# Tractive_System_Board_Rev6.net
KiCad netlist of a schematic drawn in EAGLE
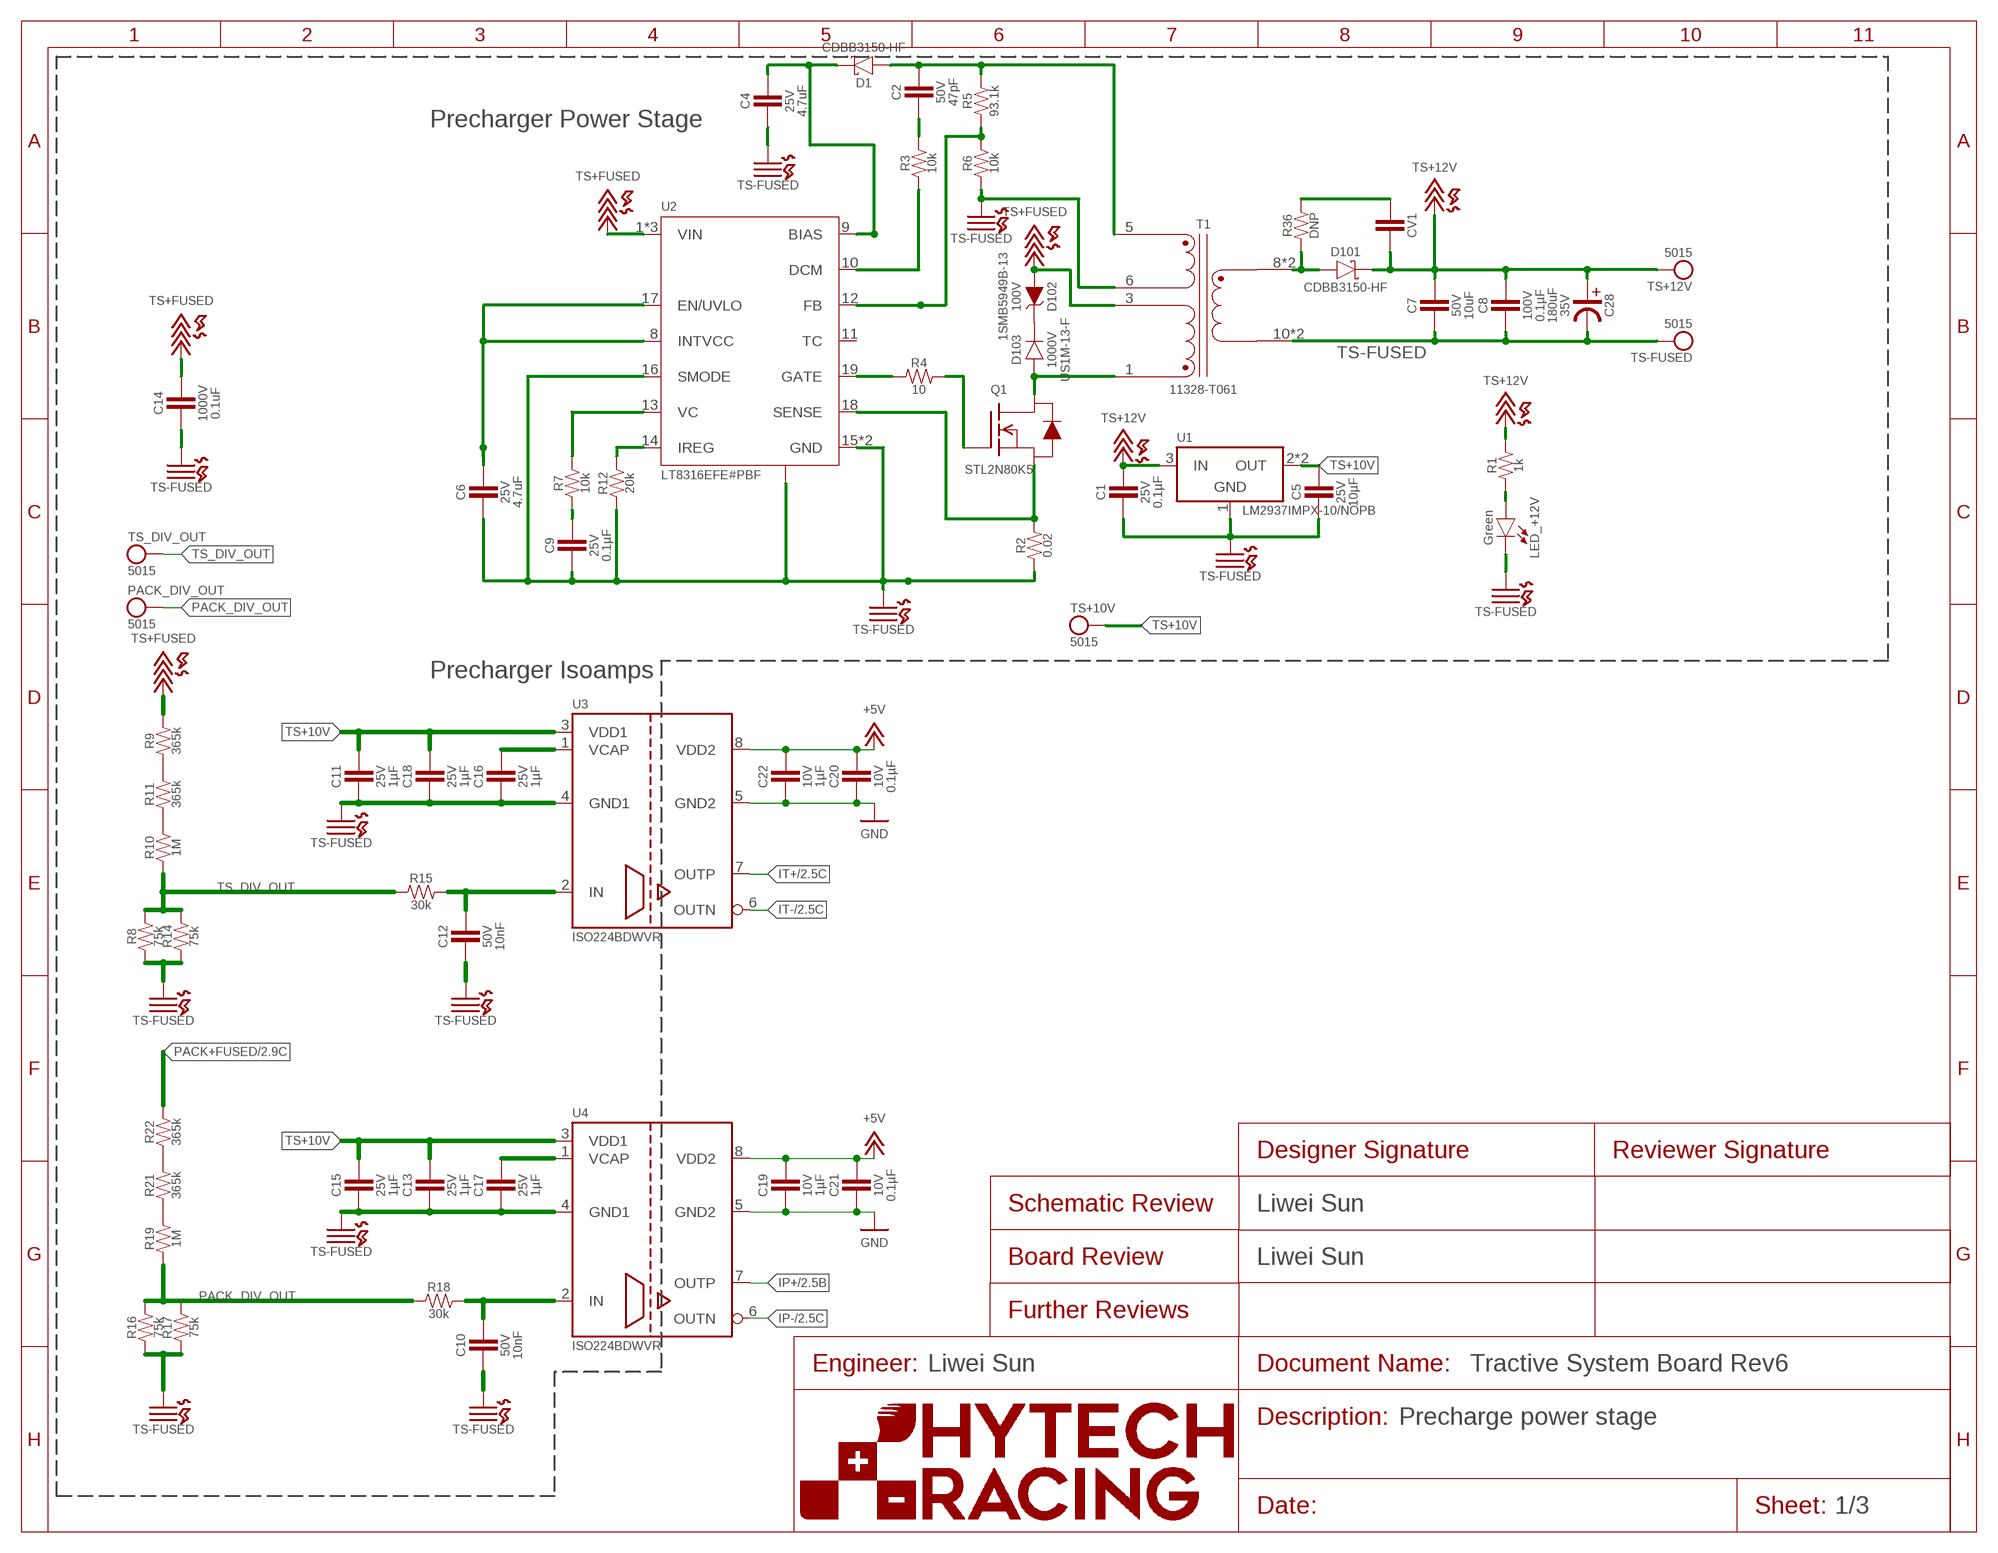
[diagram p0: schematic, sheet 1]
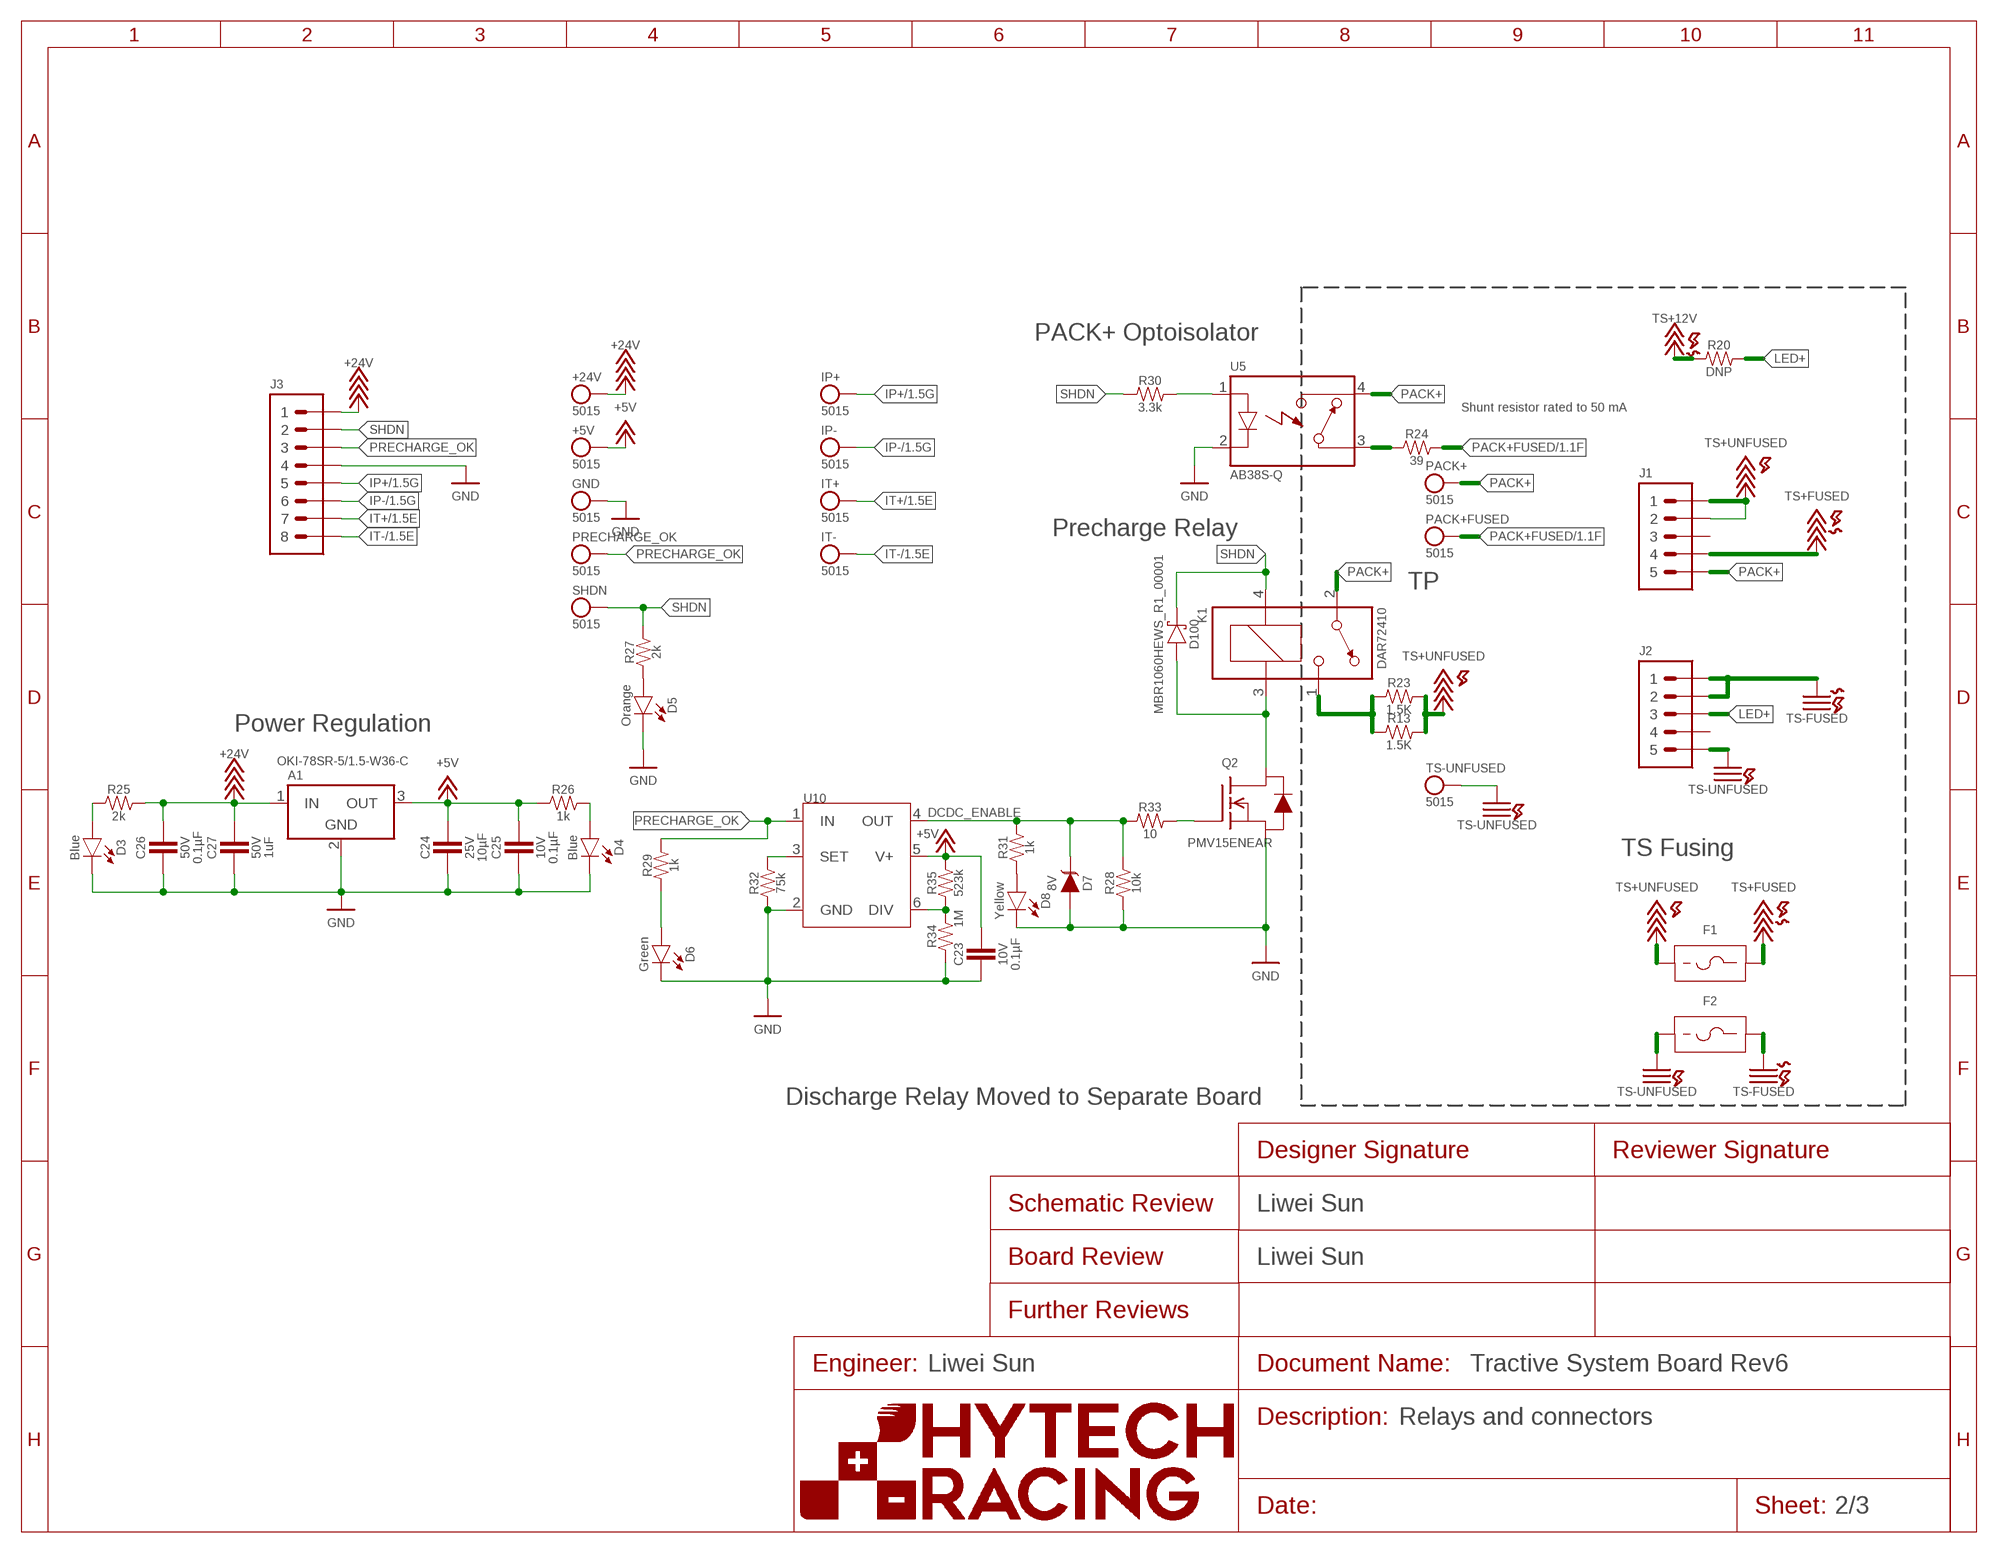
[diagram p1: schematic, sheet 2]
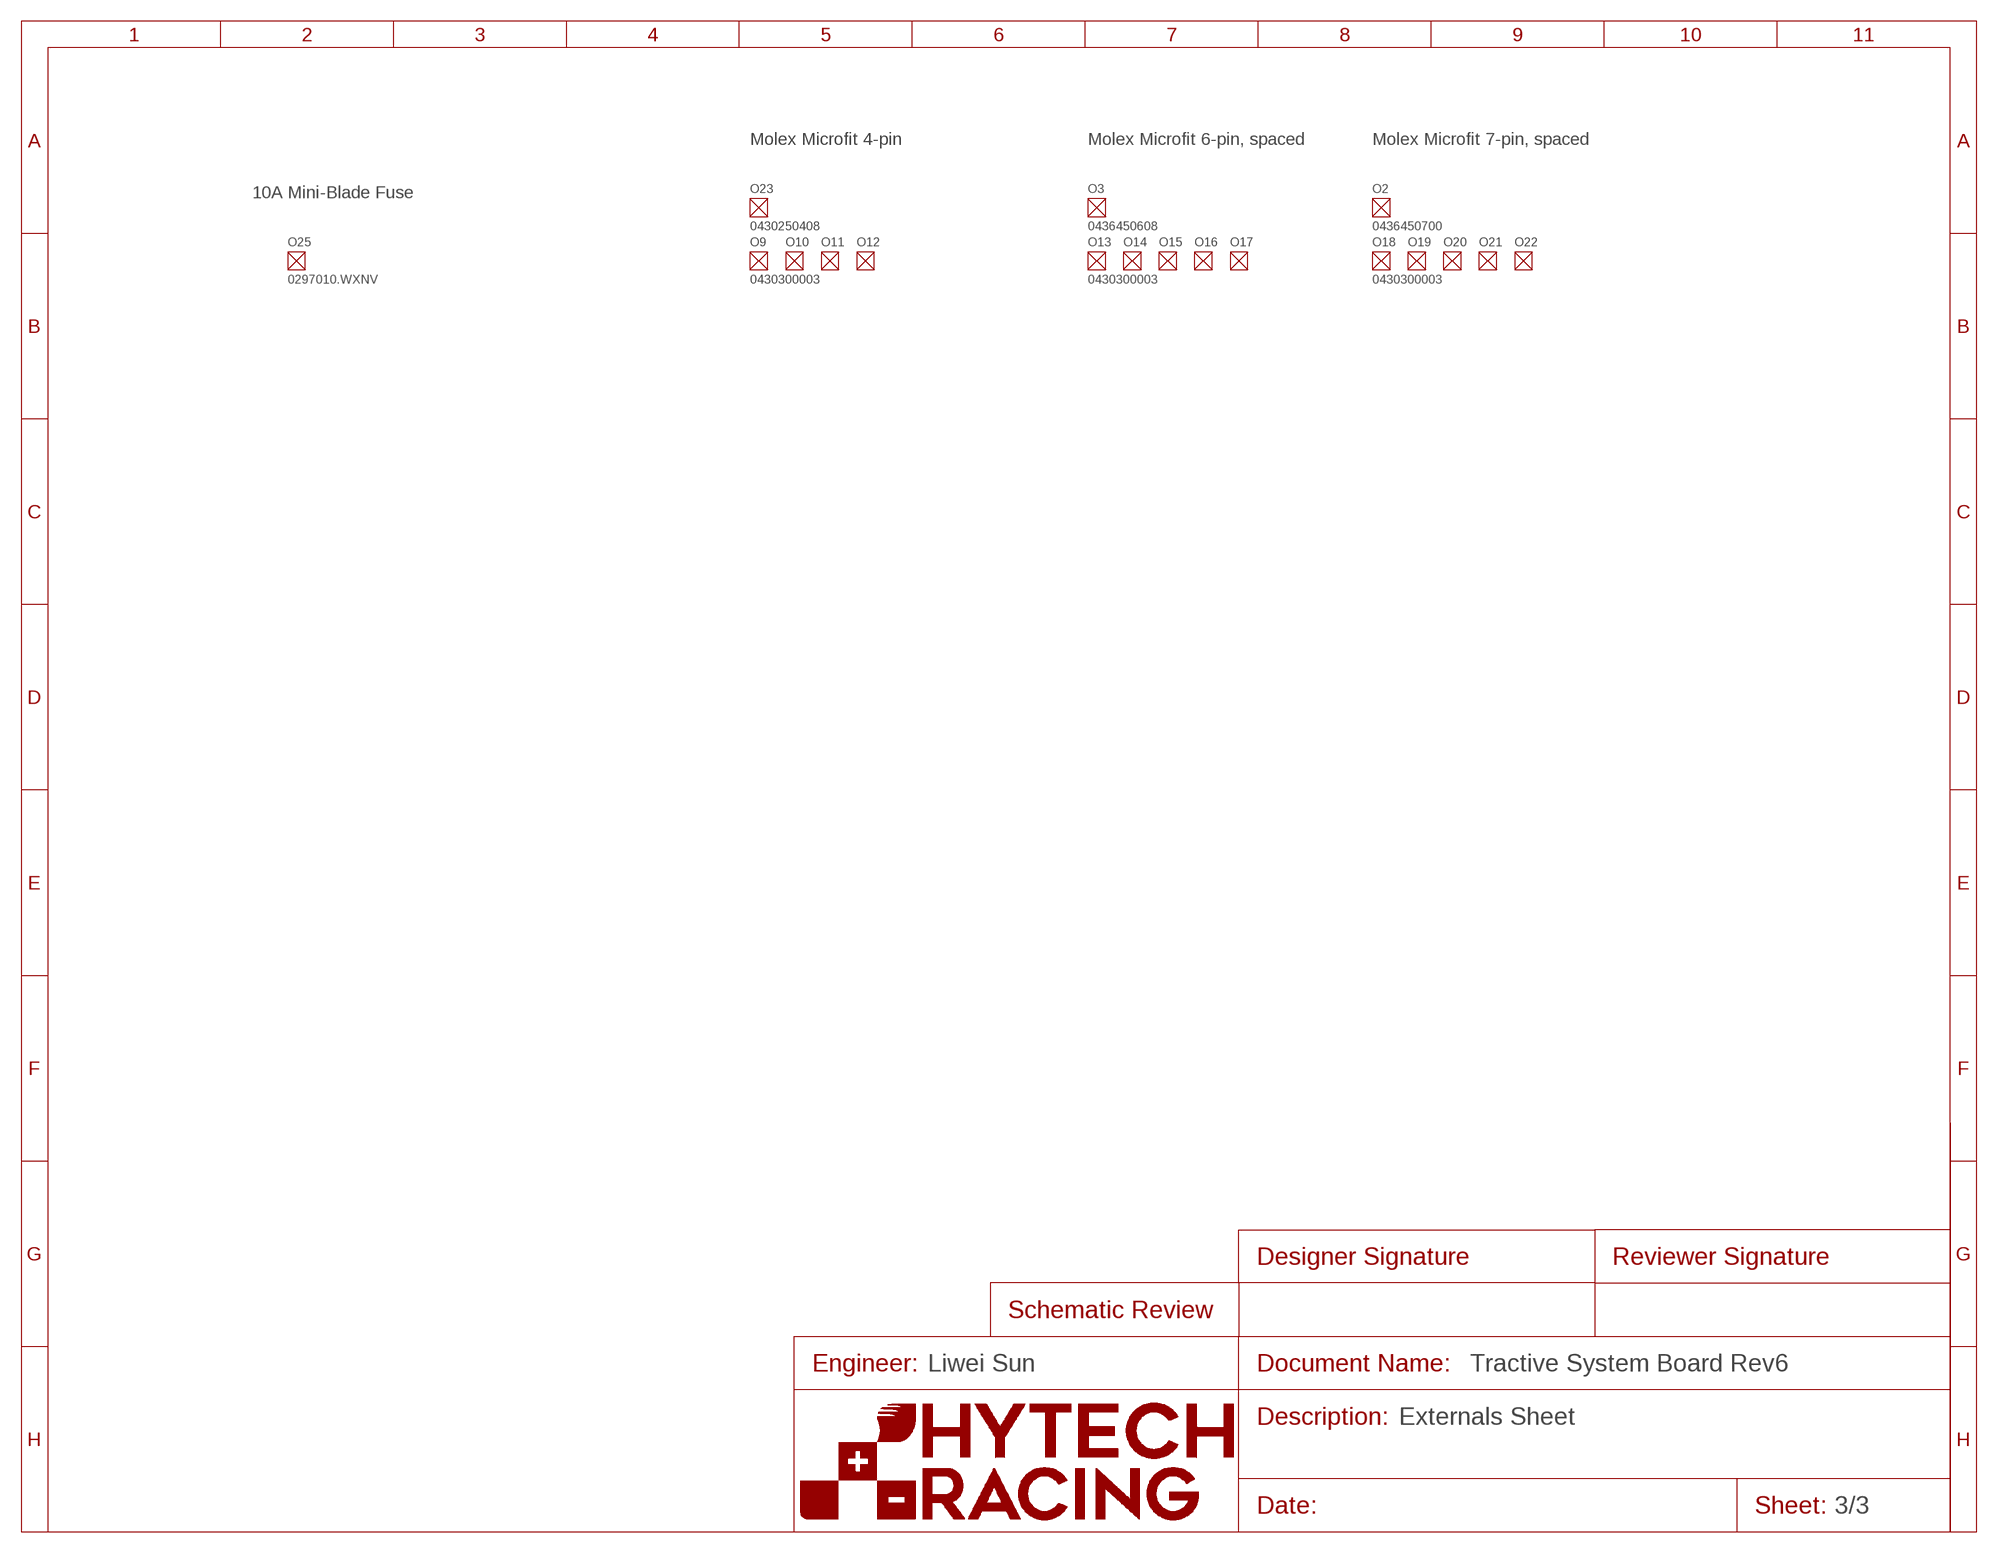
[diagram p2: schematic, sheet 3]

(export (version "E")
  (design (tool "Eeschema 10.0.6"))
  (components
    (comp (ref "+5V")
      (value "TEST_POINT")
      (footprint "eagle-import:5015")
      (fields (field (name "MPN") "5015") (field (name "MANUFACTURER") "Keystone Electronics"))
      (libsource (lib "eagle-import") (part "TEST_POINT"))
    )
    (comp (ref "+24V")
      (value "TEST_POINT")
      (footprint "eagle-import:5015")
      (fields (field (name "MPN") "5015") (field (name "MANUFACTURER") "Keystone Electronics"))
      (libsource (lib "eagle-import") (part "TEST_POINT"))
    )
    (comp (ref "A1")
      (value "VOLTAGE_REGULATOR_MODULE_OKI-78SR_5V")
      (footprint "eagle-import:OKI-78SR")
      (fields
        (field (name "MANUFACTURER") "Murata Power Solutions Inc.")
        (field (name "MPN") "OKI-78SR-5/1.5-W36-C")
      )
      (libsource (lib "eagle-import") (part "VOLTAGE_REGULATOR_MODULE_?_OKI-78SR5V"))
    )
    (comp (ref "C23")
      (value "CAPACITOR_0603_10V_0.1UF")
      (footprint "eagle-import:0603-CAP")
      (fields
        (field (name "CAPACITANCE") "0.1µF")
        (field (name "MANUFACTURER") "Vishay Vitramon")
        (field (name "MPN") "VJ0603Y104JXQPW1BC")
        (field (name "TOLERANCE") "5%")
        (field (name "VOLTAGE") "10V")
      )
      (libsource (lib "eagle-import") (part "CAPACITOR_?_060310V_0.1UF"))
    )
    (comp (ref "C24")
      (value "CAPACITOR_0603_25V_10UF")
      (footprint "eagle-import:0603-CAP")
      (fields
        (field (name "CAPACITANCE") "10µF")
        (field (name "MANUFACTURER") "Murata Electronics")
        (field (name "MPN") "GRM188R61E106MA73D")
        (field (name "TOLERANCE") "20%")
        (field (name "VOLTAGE") "25V")
      )
      (libsource (lib "eagle-import") (part "CAPACITOR_?_060325V_10UF"))
    )
    (comp (ref "C25")
      (value "CAPACITOR_0603_10V_0.1UF")
      (footprint "eagle-import:0603-CAP")
      (fields
        (field (name "CAPACITANCE") "0.1µF")
        (field (name "MANUFACTURER") "Vishay Vitramon")
        (field (name "MPN") "VJ0603Y104JXQPW1BC")
        (field (name "TOLERANCE") "5%")
        (field (name "VOLTAGE") "10V")
      )
      (libsource (lib "eagle-import") (part "CAPACITOR_?_060310V_0.1UF"))
    )
    (comp (ref "C26")
      (value "CAPACITOR_0603_50V_0.1UF")
      (footprint "eagle-import:0603-CAP")
      (fields
        (field (name "CAPACITANCE") "0.1µF")
        (field (name "MANUFACTURER") "Yageo")
        (field (name "MPN") "CC0603KRX7R9BB104")
        (field (name "TOLERANCE") "10%")
        (field (name "VOLTAGE") "50V")
      )
      (libsource (lib "eagle-import") (part "CAPACITOR_?_060350V_0.1UF"))
    )
    (comp (ref "C27")
      (value "CAPACITOR_0603_50V_1UF")
      (footprint "eagle-import:0603-CAP")
      (fields
        (field (name "CAPACITANCE") "1uF")
        (field (name "MANUFACTURER") "Taiyo Yuden")
        (field (name "MPN") "UMK107BJ105KA-T")
        (field (name "TOLERANCE") "10%")
        (field (name "VOLTAGE") "50V")
      )
      (libsource (lib "eagle-import") (part "CAPACITOR_?_060350V_1UF"))
    )
    (comp (ref "D3")
      (value "LED_0603_BLUE")
      (footprint "eagle-import:0603-LED")
      (fields
        (field (name "COLOR") "Blue")
        (field (name "MANUFACTURER") "Kingbright")
        (field (name "MPN") "APT1608VBC/D")
      )
      (libsource (lib "eagle-import") (part "LED_?_0603BLUE"))
    )
    (comp (ref "D4")
      (value "LED_0603_BLUE")
      (footprint "eagle-import:0603-LED")
      (fields
        (field (name "COLOR") "Blue")
        (field (name "MANUFACTURER") "Kingbright")
        (field (name "MPN") "APT1608VBC/D")
      )
      (libsource (lib "eagle-import") (part "LED_?_0603BLUE"))
    )
    (comp (ref "D5")
      (value "LED_0603_ORANGE")
      (footprint "eagle-import:0603-LED")
      (fields
        (field (name "COLOR") "Orange")
        (field (name "MANUFACTURER") "Kingbright")
        (field (name "MPN") "APT1608SECK")
      )
      (libsource (lib "eagle-import") (part "LED_?_0603ORANGE"))
    )
    (comp (ref "D6")
      (value "LED_0603_GREEN")
      (footprint "eagle-import:0603-LED")
      (fields
        (field (name "COLOR") "Green")
        (field (name "MANUFACTURER") "Kingbright")
        (field (name "MPN") "APT1608ZGCK")
      )
      (libsource (lib "eagle-import") (part "LED_?_0603GREEN"))
    )
    (comp (ref "D7")
      (value "TVS__8V")
      (footprint "eagle-import:SOT-23")
      (fields
        (field (name "MANUFACTURER") "Vishay General Semiconductor - Diodes Division")
        (field (name "MPN") "GSOT08-E3-08")
        (field (name "VOLTAGE") "8V")
      )
      (libsource (lib "eagle-import") (part "TVS_?_8V"))
    )
    (comp (ref "D8")
      (value "LED_0603_YELLOW")
      (footprint "eagle-import:0603-LED")
      (fields
        (field (name "COLOR") "Yellow")
        (field (name "MANUFACTURER") "Kingbright")
        (field (name "MPN") "APT1608SYCK/J3-PRV")
      )
      (libsource (lib "eagle-import") (part "LED_?_0603YELLOW"))
    )
    (comp (ref "D100")
      (value "SCHOTTKY_SOD323_60V")
      (footprint "eagle-import:SOD-323")
      (fields
        (field (name "MANUFACTURER") "Panjit International Inc.")
        (field (name "MPN") "MBR1060HEWS_R1_00001")
        (field (name "VOLTAGE") "60V")
      )
      (libsource (lib "eagle-import") (part "SCHOTTKY_?_SOD32360V"))
    )
    (comp (ref "F1")
      (value "FUSE_HOLDER_122")
      (footprint "eagle-import:122")
      (fields (field (name "MPN") "01220088Z") (field (name "MANUFACTURER") "Littelfuse"))
      (libsource (lib "eagle-import") (part "FUSE_HOLDER_122"))
    )
    (comp (ref "F2")
      (value "FUSE_HOLDER_122")
      (footprint "eagle-import:122")
      (fields (field (name "MPN") "01220088Z") (field (name "MANUFACTURER") "Littelfuse"))
      (libsource (lib "eagle-import") (part "FUSE_HOLDER_122"))
    )
    (comp (ref "GND")
      (value "TEST_POINT")
      (footprint "eagle-import:5015")
      (fields (field (name "MPN") "5015") (field (name "MANUFACTURER") "Keystone Electronics"))
      (libsource (lib "eagle-import") (part "TEST_POINT"))
    )
    (comp (ref "IP+")
      (value "TEST_POINT")
      (footprint "eagle-import:5015")
      (fields (field (name "MPN") "5015") (field (name "MANUFACTURER") "Keystone Electronics"))
      (libsource (lib "eagle-import") (part "TEST_POINT"))
    )
    (comp (ref "IP-")
      (value "TEST_POINT")
      (footprint "eagle-import:5015")
      (fields (field (name "MPN") "5015") (field (name "MANUFACTURER") "Keystone Electronics"))
      (libsource (lib "eagle-import") (part "TEST_POINT"))
    )
    (comp (ref "IT+")
      (value "TEST_POINT")
      (footprint "eagle-import:5015")
      (fields (field (name "MPN") "5015") (field (name "MANUFACTURER") "Keystone Electronics"))
      (libsource (lib "eagle-import") (part "TEST_POINT"))
    )
    (comp (ref "IT-")
      (value "TEST_POINT")
      (footprint "eagle-import:5015")
      (fields (field (name "MPN") "5015") (field (name "MANUFACTURER") "Keystone Electronics"))
      (libsource (lib "eagle-import") (part "TEST_POINT"))
    )
    (comp (ref "J1")
      (value "CONNECTOR-5_MICRO_V7S_")
      (footprint "eagle-import:MOLEX_MICROFIT_PTH_VERTICAL_07_SINGLE_SPACED")
      (fields (field (name "MPN") "2165713007") (field (name "MANUFACTURER") "Molex"))
      (libsource (lib "eagle-import") (part "CONNECTOR-5_?_MICRO_V7S"))
    )
    (comp (ref "J2")
      (value "CONNECTOR-5_MICRO_V6S_")
      (footprint "eagle-import:MOLEX_MICROFIT_PTH_VERTICAL_06_SINGLE_SPACED")
      (fields (field (name "MPN") "2165713006") (field (name "MANUFACTURER") "Molex"))
      (libsource (lib "eagle-import") (part "CONNECTOR-5_?_MICRO_V6S"))
    )
    (comp (ref "J3")
      (value "CONNECTOR-8_μF_T_V_BLACK")
      (footprint "eagle-import:MOLEX_MICROFIT_PTH_VERTICAL_08_DUAL")
      (fields (field (name "MANUFACTURER") "Molex") (field (name "MPN") "430450814"))
      (libsource (lib "eagle-import") (part "CONNECTOR-8_?_μF_T_VBLACK"))
    )
    (comp (ref "K1")
      (value "RELAY_SPST_NO_D_24")
      (footprint "eagle-import:D")
      (fields (field (name "MANUFACTURER") "Sensata-Cynergy3") (field (name "MPN") "DAR72410"))
      (libsource (lib "eagle-import") (part "RELAY_SPST_NO_?D_24"))
    )
    (comp (ref "PACK+")
      (value "TEST_POINT")
      (footprint "eagle-import:5015")
      (fields (field (name "MPN") "5015") (field (name "MANUFACTURER") "Keystone Electronics"))
      (libsource (lib "eagle-import") (part "TEST_POINT"))
    )
    (comp (ref "PACK+FUSED")
      (value "TEST_POINT")
      (footprint "eagle-import:5015")
      (fields (field (name "MPN") "5015") (field (name "MANUFACTURER") "Keystone Electronics"))
      (libsource (lib "eagle-import") (part "TEST_POINT"))
    )
    (comp (ref "PRECHARGE_OK")
      (value "TEST_POINT")
      (footprint "eagle-import:5015")
      (fields (field (name "MPN") "5015") (field (name "MANUFACTURER") "Keystone Electronics"))
      (libsource (lib "eagle-import") (part "TEST_POINT"))
    )
    (comp (ref "Q2")
      (value "TRANSISTOR_N_MOS__PMV15ENEA")
      (footprint "eagle-import:SOT-23")
      (fields (field (name "MANUFACTURER") "Nexperia USA Inc.") (field (name "MPN") "PMV15ENEAR"))
      (libsource (lib "eagle-import") (part "TRANSISTOR_N_MOS_?_PMV15ENEA"))
    )
    (comp (ref "R13")
      (value "RESISTOR_B20-SHORTENED_1.5K")
      (footprint "eagle-import:B20-SHORTENED")
      (fields
        (field (name "MANUFACTURER") "Ohmite")
        (field (name "MPN") "B20J1K5E")
        (field (name "POWER") "20W")
        (field (name "RESISTANCE") "1.5K")
      )
      (libsource (lib "eagle-import") (part "RESISTOR_?_B20-SHORTENED1.5K"))
    )
    (comp (ref "R20")
      (value "RESISTOR_0603_DNP")
      (footprint "eagle-import:0603-RES")
      (fields (field (name "RESISTANCE") "DNP"))
      (libsource (lib "eagle-import") (part "RESISTOR_?_0603DNP"))
    )
    (comp (ref "R23")
      (value "RESISTOR_B20-SHORTENED_1.5K")
      (footprint "eagle-import:B20-SHORTENED")
      (fields
        (field (name "MANUFACTURER") "Ohmite")
        (field (name "MPN") "B20J1K5E")
        (field (name "POWER") "20W")
        (field (name "RESISTANCE") "1.5K")
      )
      (libsource (lib "eagle-import") (part "RESISTOR_?_B20-SHORTENED1.5K"))
    )
    (comp (ref "R24")
      (value "RESISTOR_0603_39")
      (footprint "eagle-import:0603-RES")
      (fields
        (field (name "MANUFACTURER") "Yageo")
        (field (name "MPN") "RT0603BRD0739RL")
        (field (name "POWER") "0.1W")
        (field (name "RESISTANCE") "39")
      )
      (libsource (lib "eagle-import") (part "RESISTOR_?_060339"))
    )
    (comp (ref "R25")
      (value "RESISTOR_0603_2K")
      (footprint "eagle-import:0603-RES")
      (fields
        (field (name "MANUFACTURER") "Panasonic Electronic Components")
        (field (name "MPN") "ERJ-UP3F2001V")
        (field (name "POWER") "0.25W")
        (field (name "RESISTANCE") "2k")
      )
      (libsource (lib "eagle-import") (part "RESISTOR_?_06032K"))
    )
    (comp (ref "R26")
      (value "RESISTOR_0603_1K")
      (footprint "eagle-import:0603-RES")
      (fields
        (field (name "MANUFACTURER") "TE Connectivity Passive Product")
        (field (name "MPN") " CPF-A-0603B1K0E")
        (field (name "POWER") "0.0625W")
        (field (name "RESISTANCE") "1k")
      )
      (libsource (lib "eagle-import") (part "RESISTOR_?_06031K"))
    )
    (comp (ref "R27")
      (value "RESISTOR_0603_2K")
      (footprint "eagle-import:0603-RES")
      (fields
        (field (name "MANUFACTURER") "Panasonic Electronic Components")
        (field (name "MPN") "ERJ-UP3F2001V")
        (field (name "POWER") "0.25W")
        (field (name "RESISTANCE") "2k")
      )
      (libsource (lib "eagle-import") (part "RESISTOR_?_06032K"))
    )
    (comp (ref "R28")
      (value "RESISTOR_0603_10K")
      (footprint "eagle-import:0603-RES")
      (fields
        (field (name "MANUFACTURER") "Panasonic Electronic Components")
        (field (name "MPN") "ERA-3ARB103V")
        (field (name "POWER") "0.1W")
        (field (name "RESISTANCE") "10k")
      )
      (libsource (lib "eagle-import") (part "RESISTOR_?_060310K"))
    )
    (comp (ref "R29")
      (value "RESISTOR_0603_1K")
      (footprint "eagle-import:0603-RES")
      (fields
        (field (name "MANUFACTURER") "TE Connectivity Passive Product")
        (field (name "MPN") " CPF-A-0603B1K0E")
        (field (name "POWER") "0.0625W")
        (field (name "RESISTANCE") "1k")
      )
      (libsource (lib "eagle-import") (part "RESISTOR_?_06031K"))
    )
    (comp (ref "R30")
      (value "RESISTOR_0603_3.3K")
      (footprint "eagle-import:0603-RES")
      (fields
        (field (name "MANUFACTURER") "Panasonic Electronic Components")
        (field (name "MPN") "ERJ-PB3D3301V")
        (field (name "POWER") "0.3W")
        (field (name "RESISTANCE") "3.3k")
      )
      (libsource (lib "eagle-import") (part "RESISTOR_?_06033.3K"))
    )
    (comp (ref "R31")
      (value "RESISTOR_0603_1K")
      (footprint "eagle-import:0603-RES")
      (fields
        (field (name "MANUFACTURER") "TE Connectivity Passive Product")
        (field (name "MPN") " CPF-A-0603B1K0E")
        (field (name "POWER") "0.0625W")
        (field (name "RESISTANCE") "1k")
      )
      (libsource (lib "eagle-import") (part "RESISTOR_?_06031K"))
    )
    (comp (ref "R32")
      (value "RESISTOR_0603_75K")
      (footprint "eagle-import:0603-RES")
      (fields
        (field (name "MANUFACTURER") "Yageo")
        (field (name "MPN") "RT0603BRE0775KL")
        (field (name "POWER") "0.1W")
        (field (name "RESISTANCE") "75k")
      )
      (libsource (lib "eagle-import") (part "RESISTOR_?_060375K"))
    )
    (comp (ref "R33")
      (value "RESISTOR_0603_10")
      (footprint "eagle-import:0603-RES")
      (fields
        (field (name "MANUFACTURER") "Yageo")
        (field (name "MPN") "RC0603FR-0710RL")
        (field (name "POWER") "0.1W")
        (field (name "RESISTANCE") "10")
      )
      (libsource (lib "eagle-import") (part "RESISTOR_?_060310"))
    )
    (comp (ref "R34")
      (value "RESISTOR_0805_1M")
      (footprint "eagle-import:0805-RES")
      (fields
        (field (name "MANUFACTURER") "Panasonic Electronic Components")
        (field (name "MPN") "ERJ-PB6B1004V")
        (field (name "POWER") "0.25W")
        (field (name "RESISTANCE") "1M")
      )
      (libsource (lib "eagle-import") (part "RESISTOR_?_08051M"))
    )
    (comp (ref "R35")
      (value "RESISTOR_0805_523K")
      (footprint "eagle-import:0805-RES")
      (fields
        (field (name "MANUFACTURER") "Panasonic Electronic Components")
        (field (name "MPN") "ERJ-PB6B5233V")
        (field (name "POWER") "0.25W")
        (field (name "RESISTANCE") "523k")
      )
      (libsource (lib "eagle-import") (part "RESISTOR_?_0805523K"))
    )
    (comp (ref "SHDN")
      (value "TEST_POINT")
      (footprint "eagle-import:5015")
      (fields (field (name "MPN") "5015") (field (name "MANUFACTURER") "Keystone Electronics"))
      (libsource (lib "eagle-import") (part "TEST_POINT"))
    )
    (comp (ref "TS-UNFUSED")
      (value "TEST_POINT")
      (footprint "eagle-import:5015")
      (fields (field (name "MPN") "5015") (field (name "MANUFACTURER") "Keystone Electronics"))
      (libsource (lib "eagle-import") (part "TEST_POINT"))
    )
    (comp (ref "U5")
      (value "RELAY_SOLIDSTATE_NO_AB38S-Q-AIRGAP")
      (footprint "eagle-import:SOP-04-AIRGAP")
      (fields
        (field (name "MPN") "AB38S-Q")
        (field (name "MANUFACTURER") "Comus International")
        (field (name "VOLTAGE") "600V")
      )
      (libsource (lib "eagle-import") (part "RELAY_SOLIDSTATE_NO_AB38S-Q-AIRGAP"))
    )
    (comp (ref "U10")
      (value "LTC6994-2")
      (footprint "eagle-import:SOT-23-6")
      (libsource (lib "eagle-import") (part "LTC6994-2"))
    )
    (comp (ref "C1")
      (value "CAPACITOR_0603_25V_0.1UF")
      (footprint "eagle-import:0603-CAP")
      (fields
        (field (name "CAPACITANCE") "0.1µF")
        (field (name "MANUFACTURER") "Samsung Electro-Mechanics")
        (field (name "MPN") "CL10B104KA8NNNC")
        (field (name "TOLERANCE") "10%")
        (field (name "VOLTAGE") "25V")
      )
      (libsource (lib "eagle-import") (part "CAPACITOR_?_060325V_0.1UF"))
    )
    (comp (ref "C2")
      (value "CAPACITOR_0603_50V_47PF")
      (footprint "eagle-import:0603-CAP")
      (fields
        (field (name "CAPACITANCE") "47pF")
        (field (name "MANUFACTURER") "TDK Corporation")
        (field (name "MPN") "CGA3E2NP01H470J080AA")
        (field (name "TOLERANCE") "5%")
        (field (name "VOLTAGE") "50V")
      )
      (libsource (lib "eagle-import") (part "CAPACITOR_?_060350V_47PF"))
    )
    (comp (ref "C4")
      (value "CAPACITOR_0603_25V_4.7UF")
      (footprint "eagle-import:0603-CAP")
      (fields
        (field (name "CAPACITANCE") "4.7uF")
        (field (name "MANUFACTURER") "TDK Corporation")
        (field (name "MPN") " C1608X5R1E475K080AC")
        (field (name "TOLERANCE") "10%")
        (field (name "VOLTAGE") "25V")
      )
      (libsource (lib "eagle-import") (part "CAPACITOR_?_060325V_4.7UF"))
    )
    (comp (ref "C5")
      (value "CAPACITOR_0603_25V_10UF")
      (footprint "eagle-import:0603-CAP")
      (fields
        (field (name "CAPACITANCE") "10µF")
        (field (name "MANUFACTURER") "Murata Electronics")
        (field (name "MPN") "GRM188R61E106MA73D")
        (field (name "TOLERANCE") "20%")
        (field (name "VOLTAGE") "25V")
      )
      (libsource (lib "eagle-import") (part "CAPACITOR_?_060325V_10UF"))
    )
    (comp (ref "C6")
      (value "CAPACITOR_0603_25V_4.7UF")
      (footprint "eagle-import:0603-CAP")
      (fields
        (field (name "CAPACITANCE") "4.7uF")
        (field (name "MANUFACTURER") "TDK Corporation")
        (field (name "MPN") " C1608X5R1E475K080AC")
        (field (name "TOLERANCE") "10%")
        (field (name "VOLTAGE") "25V")
      )
      (libsource (lib "eagle-import") (part "CAPACITOR_?_060325V_4.7UF"))
    )
    (comp (ref "C7")
      (value "CAPACITOR_0805_50V_10UF")
      (footprint "eagle-import:0805-CAP")
      (fields
        (field (name "CAPACITANCE") "10uF")
        (field (name "MANUFACTURER") "Murata")
        (field (name "MPN") " GRM21BR61H106KE43L")
        (field (name "TOLERANCE") "10%")
        (field (name "VOLTAGE") "50V")
      )
      (libsource (lib "eagle-import") (part "CAPACITOR_?_080550V_10UF"))
    )
    (comp (ref "C8")
      (value "CAPACITOR_0603_100V_0.1UF")
      (footprint "eagle-import:0603-CAP")
      (fields
        (field (name "CAPACITANCE") "0.1µF")
        (field (name "MANUFACTURER") "Yageo")
        (field (name "MPN") "CC0603KRX7R0BB104")
        (field (name "TOLERANCE") "10%")
        (field (name "VOLTAGE") "100V")
      )
      (libsource (lib "eagle-import") (part "CAPACITOR_?_0603100V_0.1UF"))
    )
    (comp (ref "C9")
      (value "CAPACITOR_0603_25V_0.1UF")
      (footprint "eagle-import:0603-CAP")
      (fields
        (field (name "CAPACITANCE") "0.1µF")
        (field (name "MANUFACTURER") "Samsung Electro-Mechanics")
        (field (name "MPN") "CL10B104KA8NNNC")
        (field (name "TOLERANCE") "10%")
        (field (name "VOLTAGE") "25V")
      )
      (libsource (lib "eagle-import") (part "CAPACITOR_?_060325V_0.1UF"))
    )
    (comp (ref "C10")
      (value "CAPACITOR_0603_50V_10NF")
      (footprint "eagle-import:0603-CAP")
      (fields
        (field (name "CAPACITANCE") "10nF")
        (field (name "MANUFACTURER") "TDK Corporation")
        (field (name "MPN") "C1608C0G1H103J080AA")
        (field (name "TOLERANCE") "5%")
        (field (name "VOLTAGE") "50V")
      )
      (libsource (lib "eagle-import") (part "CAPACITOR_?_060350V_10NF"))
    )
    (comp (ref "C11")
      (value "CAPACITOR_0603_25V_1UF")
      (footprint "eagle-import:0603-CAP")
      (fields
        (field (name "CAPACITANCE") "1µF")
        (field (name "MANUFACTURER") "Samsung Electro-Mechanics")
        (field (name "MPN") "CL10B105KA8NNNC")
        (field (name "TOLERANCE") "10%")
        (field (name "VOLTAGE") "25V")
      )
      (libsource (lib "eagle-import") (part "CAPACITOR_?_060325V_1UF"))
    )
    (comp (ref "C12")
      (value "CAPACITOR_0603_50V_10NF")
      (footprint "eagle-import:0603-CAP")
      (fields
        (field (name "CAPACITANCE") "10nF")
        (field (name "MANUFACTURER") "TDK Corporation")
        (field (name "MPN") "C1608C0G1H103J080AA")
        (field (name "TOLERANCE") "5%")
        (field (name "VOLTAGE") "50V")
      )
      (libsource (lib "eagle-import") (part "CAPACITOR_?_060350V_10NF"))
    )
    (comp (ref "C13")
      (value "CAPACITOR_0603_25V_1UF")
      (footprint "eagle-import:0603-CAP")
      (fields
        (field (name "CAPACITANCE") "1µF")
        (field (name "MANUFACTURER") "Samsung Electro-Mechanics")
        (field (name "MPN") "CL10B105KA8NNNC")
        (field (name "TOLERANCE") "10%")
        (field (name "VOLTAGE") "25V")
      )
      (libsource (lib "eagle-import") (part "CAPACITOR_?_060325V_1UF"))
    )
    (comp (ref "C14")
      (value "CAPACITOR_1812_1000V_0.1UF")
      (footprint "eagle-import:1812-CAP")
      (fields
        (field (name "CAPACITANCE") "0.1uF")
        (field (name "MANUFACTURER") "KEMET")
        (field (name "MPN") "C1812W104KDRAC7800")
        (field (name "TOLERANCE") "10%")
        (field (name "VOLTAGE") "1000V")
      )
      (libsource (lib "eagle-import") (part "CAPACITOR_?_18121000V_0.1UF"))
    )
    (comp (ref "C15")
      (value "CAPACITOR_0603_25V_1UF")
      (footprint "eagle-import:0603-CAP")
      (fields
        (field (name "CAPACITANCE") "1µF")
        (field (name "MANUFACTURER") "Samsung Electro-Mechanics")
        (field (name "MPN") "CL10B105KA8NNNC")
        (field (name "TOLERANCE") "10%")
        (field (name "VOLTAGE") "25V")
      )
      (libsource (lib "eagle-import") (part "CAPACITOR_?_060325V_1UF"))
    )
    (comp (ref "C16")
      (value "CAPACITOR_0603_25V_1UF")
      (footprint "eagle-import:0603-CAP")
      (fields
        (field (name "CAPACITANCE") "1µF")
        (field (name "MANUFACTURER") "Samsung Electro-Mechanics")
        (field (name "MPN") "CL10B105KA8NNNC")
        (field (name "TOLERANCE") "10%")
        (field (name "VOLTAGE") "25V")
      )
      (libsource (lib "eagle-import") (part "CAPACITOR_?_060325V_1UF"))
    )
    (comp (ref "C17")
      (value "CAPACITOR_0603_25V_1UF")
      (footprint "eagle-import:0603-CAP")
      (fields
        (field (name "CAPACITANCE") "1µF")
        (field (name "MANUFACTURER") "Samsung Electro-Mechanics")
        (field (name "MPN") "CL10B105KA8NNNC")
        (field (name "TOLERANCE") "10%")
        (field (name "VOLTAGE") "25V")
      )
      (libsource (lib "eagle-import") (part "CAPACITOR_?_060325V_1UF"))
    )
    (comp (ref "C18")
      (value "CAPACITOR_0603_25V_1UF")
      (footprint "eagle-import:0603-CAP")
      (fields
        (field (name "CAPACITANCE") "1µF")
        (field (name "MANUFACTURER") "Samsung Electro-Mechanics")
        (field (name "MPN") "CL10B105KA8NNNC")
        (field (name "TOLERANCE") "10%")
        (field (name "VOLTAGE") "25V")
      )
      (libsource (lib "eagle-import") (part "CAPACITOR_?_060325V_1UF"))
    )
    (comp (ref "C19")
      (value "CAPACITOR_0603_10V_1UF")
      (footprint "eagle-import:0603-CAP")
      (fields
        (field (name "CAPACITANCE") "1µF")
        (field (name "MANUFACTURER") "Yageo")
        (field (name "MPN") "CC0603KRX7R6BB105")
        (field (name "TOLERANCE") "10%")
        (field (name "VOLTAGE") "10V")
      )
      (libsource (lib "eagle-import") (part "CAPACITOR_?_060310V_1UF"))
    )
    (comp (ref "C20")
      (value "CAPACITOR_0603_10V_0.1UF")
      (footprint "eagle-import:0603-CAP")
      (fields
        (field (name "CAPACITANCE") "0.1µF")
        (field (name "MANUFACTURER") "Vishay Vitramon")
        (field (name "MPN") "VJ0603Y104JXQPW1BC")
        (field (name "TOLERANCE") "5%")
        (field (name "VOLTAGE") "10V")
      )
      (libsource (lib "eagle-import") (part "CAPACITOR_?_060310V_0.1UF"))
    )
    (comp (ref "C21")
      (value "CAPACITOR_0603_10V_0.1UF")
      (footprint "eagle-import:0603-CAP")
      (fields
        (field (name "CAPACITANCE") "0.1µF")
        (field (name "MANUFACTURER") "Vishay Vitramon")
        (field (name "MPN") "VJ0603Y104JXQPW1BC")
        (field (name "TOLERANCE") "5%")
        (field (name "VOLTAGE") "10V")
      )
      (libsource (lib "eagle-import") (part "CAPACITOR_?_060310V_0.1UF"))
    )
    (comp (ref "C22")
      (value "CAPACITOR_0603_10V_1UF")
      (footprint "eagle-import:0603-CAP")
      (fields
        (field (name "CAPACITANCE") "1µF")
        (field (name "MANUFACTURER") "Yageo")
        (field (name "MPN") "CC0603KRX7R6BB105")
        (field (name "TOLERANCE") "10%")
        (field (name "VOLTAGE") "10V")
      )
      (libsource (lib "eagle-import") (part "CAPACITOR_?_060310V_1UF"))
    )
    (comp (ref "C28")
      (value "CAPACITOR_ELECTROLYTIC_A759KR_180UF")
      (footprint "eagle-import:A759KR")
      (fields
        (field (name "CAPACITANCE") "180uF")
        (field (name "MANUFACTURER") "KEMET")
        (field (name "MPN") "A759KR187M1VAAE024")
        (field (name "TOLERANCE") "20%")
        (field (name "VOLTAGE") "35V")
      )
      (libsource (lib "eagle-import") (part "CAPACITOR_ELECTROLYTIC_?_A759KR180UF"))
    )
    (comp (ref "CV1")
      (value "CAPACITOR_VALUE")
      (footprint "eagle-import:0603-CAP")
      (libsource (lib "eagle-import") (part "CAPACITOR_VALUE"))
    )
    (comp (ref "D1")
      (value "SCHOTTKY_DO-214AA_150V")
      (footprint "eagle-import:DO-214AA")
      (fields
        (field (name "MANUFACTURER") "Comchip Technology")
        (field (name "MPN") "CDBB3150-HF")
        (field (name "VOLTAGE") "150V")
      )
      (libsource (lib "eagle-import") (part "SCHOTTKY_?_DO-214AA150V"))
    )
    (comp (ref "D101")
      (value "SCHOTTKY_DO-214AA_150V")
      (footprint "eagle-import:DO-214AA")
      (fields
        (field (name "MANUFACTURER") "Comchip Technology")
        (field (name "MPN") "CDBB3150-HF")
        (field (name "VOLTAGE") "150V")
      )
      (libsource (lib "eagle-import") (part "SCHOTTKY_?_DO-214AA150V"))
    )
    (comp (ref "D102")
      (value "ZENER_DO-214AA_100V")
      (footprint "eagle-import:DO-214AA")
      (fields
        (field (name "MANUFACTURER") "Diodes Incorporated")
        (field (name "MPN") "1SMB5949B-13")
        (field (name "VOLTAGE") "100V")
      )
      (libsource (lib "eagle-import") (part "ZENER_?_DO-214AA100V"))
    )
    (comp (ref "D103")
      (value "RECTIFIER_1000V_SMA")
      (footprint "eagle-import:SMA")
      (fields
        (field (name "MANUFACTURER") "Diodes Incorporated")
        (field (name "MPN") "US1M-13-F")
        (field (name "VOLTAGE") "1000V")
      )
      (libsource (lib "eagle-import") (part "RECTIFIER__?SMA1000V"))
    )
    (comp (ref "LED_+12V")
      (value "LED_0603_GREEN")
      (footprint "eagle-import:0603-LED")
      (fields
        (field (name "COLOR") "Green")
        (field (name "MANUFACTURER") "Kingbright")
        (field (name "MPN") "APT1608ZGCK")
      )
      (libsource (lib "eagle-import") (part "LED_?_0603GREEN"))
    )
    (comp (ref "PACK_DIV_OUT")
      (value "TEST_POINT")
      (footprint "eagle-import:5015")
      (fields (field (name "MPN") "5015") (field (name "MANUFACTURER") "Keystone Electronics"))
      (libsource (lib "eagle-import") (part "TEST_POINT"))
    )
    (comp (ref "Q1")
      (value "TRANSISTOR_N_MOS_POWERFLAT5X6_STL2N80K5")
      (footprint "eagle-import:POWERFLAT5X6")
      (fields (field (name "MANUFACTURER") "STMicroelectronics") (field (name "MPN") "STL2N80K5"))
      (libsource (lib "eagle-import") (part "TRANSISTOR_N_MOS_?_POWERFLAT5X6STL2N80K5"))
    )
    (comp (ref "R1")
      (value "RESISTOR_0603_1K")
      (footprint "eagle-import:0603-RES")
      (fields
        (field (name "MANUFACTURER") "TE Connectivity Passive Product")
        (field (name "MPN") " CPF-A-0603B1K0E")
        (field (name "POWER") "0.0625W")
        (field (name "RESISTANCE") "1k")
      )
      (libsource (lib "eagle-import") (part "RESISTOR_?_06031K"))
    )
    (comp (ref "R2")
      (value "RESISTOR_0603_0.02")
      (footprint "eagle-import:0603-RES")
      (fields
        (field (name "MANUFACTURER") "Panasonic Electronic Components")
        (field (name "MPN") "ERJ-3BWFR020V")
        (field (name "POWER") "0.33W")
        (field (name "RESISTANCE") "0.02")
      )
      (libsource (lib "eagle-import") (part "RESISTOR_?_06030.02"))
    )
    (comp (ref "R3")
      (value "RESISTOR_0603_10K")
      (footprint "eagle-import:0603-RES")
      (fields
        (field (name "MANUFACTURER") "Panasonic Electronic Components")
        (field (name "MPN") "ERA-3ARB103V")
        (field (name "POWER") "0.1W")
        (field (name "RESISTANCE") "10k")
      )
      (libsource (lib "eagle-import") (part "RESISTOR_?_060310K"))
    )
    (comp (ref "R4")
      (value "RESISTOR_0603_10")
      (footprint "eagle-import:0603-RES")
      (fields
        (field (name "MANUFACTURER") "Yageo")
        (field (name "MPN") "RC0603FR-0710RL")
        (field (name "POWER") "0.1W")
        (field (name "RESISTANCE") "10")
      )
      (libsource (lib "eagle-import") (part "RESISTOR_?_060310"))
    )
    (comp (ref "R5")
      (value "RESISTOR_0603_93.1K")
      (footprint "eagle-import:0603-RES")
      (fields
        (field (name "MANUFACTURER") "Panasonic Electronic Components")
        (field (name "MPN") "ERJ-PB3B9312V")
        (field (name "POWER") "0.2W")
        (field (name "RESISTANCE") "93.1k")
      )
      (libsource (lib "eagle-import") (part "RESISTOR_?_060393.1K"))
    )
    (comp (ref "R6")
      (value "RESISTOR_0603_10K")
      (footprint "eagle-import:0603-RES")
      (fields
        (field (name "MANUFACTURER") "Panasonic Electronic Components")
        (field (name "MPN") "ERA-3ARB103V")
        (field (name "POWER") "0.1W")
        (field (name "RESISTANCE") "10k")
      )
      (libsource (lib "eagle-import") (part "RESISTOR_?_060310K"))
    )
    (comp (ref "R7")
      (value "RESISTOR_0603_10K")
      (footprint "eagle-import:0603-RES")
      (fields
        (field (name "MANUFACTURER") "Panasonic Electronic Components")
        (field (name "MPN") "ERA-3ARB103V")
        (field (name "POWER") "0.1W")
        (field (name "RESISTANCE") "10k")
      )
      (libsource (lib "eagle-import") (part "RESISTOR_?_060310K"))
    )
    (comp (ref "R8")
      (value "RESISTOR_0805_HV75K")
      (footprint "eagle-import:0805-RES")
      (fields
        (field (name "MANUFACTURER") "Rohm Semiconductor")
        (field (name "MPN") "KTR10EZPF7502 ")
        (field (name "POWER") "0.125W")
        (field (name "RESISTANCE") "75k")
      )
      (libsource (lib "eagle-import") (part "RESISTOR_?_0805HV75K"))
    )
    (comp (ref "R9")
      (value "RESISTOR_0805_HV365K")
      (footprint "eagle-import:0805-RES")
      (fields
        (field (name "MANUFACTURER") "Rohm")
        (field (name "MPN") "KTR10EZPF3653")
        (field (name "POWER") "0.125W")
        (field (name "RESISTANCE") "365k")
      )
      (libsource (lib "eagle-import") (part "RESISTOR_?_0805HV365K"))
    )
    (comp (ref "R10")
      (value "RESISTOR_0805_HV1M")
      (footprint "eagle-import:0805-RES")
      (fields
        (field (name "MANUFACTURER") "Rohm Semiconductor")
        (field (name "MPN") "KTR10EZPF1004")
        (field (name "POWER") "0.125W")
        (field (name "RESISTANCE") "1M")
      )
      (libsource (lib "eagle-import") (part "RESISTOR_?_0805HV1M"))
    )
    (comp (ref "R11")
      (value "RESISTOR_0805_HV365K")
      (footprint "eagle-import:0805-RES")
      (fields
        (field (name "MANUFACTURER") "Rohm")
        (field (name "MPN") "KTR10EZPF3653")
        (field (name "POWER") "0.125W")
        (field (name "RESISTANCE") "365k")
      )
      (libsource (lib "eagle-import") (part "RESISTOR_?_0805HV365K"))
    )
    (comp (ref "R12")
      (value "RESISTOR_0603_20K")
      (footprint "eagle-import:0603-RES")
      (fields
        (field (name "MANUFACTURER") "Yageo")
        (field (name "MPN") "RC0603FR-0720KL")
        (field (name "POWER") "0.1 W")
        (field (name "RESISTANCE") "20k")
      )
      (libsource (lib "eagle-import") (part "RESISTOR_?_060320K"))
    )
    (comp (ref "R14")
      (value "RESISTOR_0805_HV75K")
      (footprint "eagle-import:0805-RES")
      (fields
        (field (name "MANUFACTURER") "Rohm Semiconductor")
        (field (name "MPN") "KTR10EZPF7502 ")
        (field (name "POWER") "0.125W")
        (field (name "RESISTANCE") "75k")
      )
      (libsource (lib "eagle-import") (part "RESISTOR_?_0805HV75K"))
    )
    (comp (ref "R15")
      (value "RESISTOR_0603_")
      (footprint "eagle-import:0603-RES")
      (fields
        (field (name "MANUFACTURER") "Panasonic Electronic Components")
        (field (name "MPN") "ERA-3ARB303V")
        (field (name "POWER") "0.1W")
        (field (name "RESISTANCE") "30k")
      )
      (libsource (lib "eagle-import") (part "RESISTOR_?_060330K"))
    )
    (comp (ref "R16")
      (value "RESISTOR_0805_HV75K")
      (footprint "eagle-import:0805-RES")
      (fields
        (field (name "MANUFACTURER") "Rohm Semiconductor")
        (field (name "MPN") "KTR10EZPF7502 ")
        (field (name "POWER") "0.125W")
        (field (name "RESISTANCE") "75k")
      )
      (libsource (lib "eagle-import") (part "RESISTOR_?_0805HV75K"))
    )
    (comp (ref "R17")
      (value "RESISTOR_0805_HV75K")
      (footprint "eagle-import:0805-RES")
      (fields
        (field (name "MANUFACTURER") "Rohm Semiconductor")
        (field (name "MPN") "KTR10EZPF7502 ")
        (field (name "POWER") "0.125W")
        (field (name "RESISTANCE") "75k")
      )
      (libsource (lib "eagle-import") (part "RESISTOR_?_0805HV75K"))
    )
    (comp (ref "R18")
      (value "RESISTOR_0603_")
      (footprint "eagle-import:0603-RES")
      (fields
        (field (name "MANUFACTURER") "Panasonic Electronic Components")
        (field (name "MPN") "ERA-3ARB303V")
        (field (name "POWER") "0.1W")
        (field (name "RESISTANCE") "30k")
      )
      (libsource (lib "eagle-import") (part "RESISTOR_?_060330K"))
    )
    (comp (ref "R19")
      (value "RESISTOR_0805_HV1M")
      (footprint "eagle-import:0805-RES")
      (fields
        (field (name "MANUFACTURER") "Rohm Semiconductor")
        (field (name "MPN") "KTR10EZPF1004")
        (field (name "POWER") "0.125W")
        (field (name "RESISTANCE") "1M")
      )
      (libsource (lib "eagle-import") (part "RESISTOR_?_0805HV1M"))
    )
    (comp (ref "R21")
      (value "RESISTOR_0805_HV365K")
      (footprint "eagle-import:0805-RES")
      (fields
        (field (name "MANUFACTURER") "Rohm")
        (field (name "MPN") "KTR10EZPF3653")
        (field (name "POWER") "0.125W")
        (field (name "RESISTANCE") "365k")
      )
      (libsource (lib "eagle-import") (part "RESISTOR_?_0805HV365K"))
    )
    (comp (ref "R22")
      (value "RESISTOR_0805_HV365K")
      (footprint "eagle-import:0805-RES")
      (fields
        (field (name "MANUFACTURER") "Rohm")
        (field (name "MPN") "KTR10EZPF3653")
        (field (name "POWER") "0.125W")
        (field (name "RESISTANCE") "365k")
      )
      (libsource (lib "eagle-import") (part "RESISTOR_?_0805HV365K"))
    )
    (comp (ref "R36")
      (value "RESISTOR_0603_DNP")
      (footprint "eagle-import:0603-RES")
      (fields (field (name "RESISTANCE") "DNP"))
      (libsource (lib "eagle-import") (part "RESISTOR_?_0603DNP"))
    )
    (comp (ref "T1")
      (value "TRANSFORMER(3W)")
      (footprint "eagle-import:PQ2620")
      (fields (field (name "MPN") "11328-T061") (field (name "MANUFACTURER") "Sumida"))
      (libsource (lib "eagle-import") (part "TRANSFORMER(3W)"))
    )
    (comp (ref "TS+10V")
      (value "TEST_POINT")
      (footprint "eagle-import:5015")
      (fields (field (name "MPN") "5015") (field (name "MANUFACTURER") "Keystone Electronics"))
      (libsource (lib "eagle-import") (part "TEST_POINT"))
    )
    (comp (ref "TS+12V")
      (value "TEST_POINT")
      (footprint "eagle-import:5015")
      (fields (field (name "MPN") "5015") (field (name "MANUFACTURER") "Keystone Electronics"))
      (libsource (lib "eagle-import") (part "TEST_POINT"))
    )
    (comp (ref "TS-FUSED")
      (value "TEST_POINT")
      (footprint "eagle-import:5015")
      (fields (field (name "MPN") "5015") (field (name "MANUFACTURER") "Keystone Electronics"))
      (libsource (lib "eagle-import") (part "TEST_POINT"))
    )
    (comp (ref "TS_DIV_OUT")
      (value "TEST_POINT")
      (footprint "eagle-import:5015")
      (fields (field (name "MPN") "5015") (field (name "MANUFACTURER") "Keystone Electronics"))
      (libsource (lib "eagle-import") (part "TEST_POINT"))
    )
    (comp (ref "U1")
      (value "VOLTAGE_REGULATOR_SOT-223_10V")
      (footprint "eagle-import:SOT-223")
      (fields (field (name "MANUFACTURER") "Texas Instruments") (field (name "MPN") " LM2937IMPX-10/NOPB"))
      (libsource (lib "eagle-import") (part "VOLTAGE_REGULATOR_?_SOT-22310V"))
    )
    (comp (ref "U2")
      (value "LT8316")
      (footprint "eagle-import:TSSOP-20(16)")
      (fields (field (name "MPN") "LT8316EFE#PBF") (field (name "MANUFACTURER") "Analog Devices"))
      (libsource (lib "eagle-import") (part "LT8316"))
    )
    (comp (ref "U3")
      (value "ISO224B_AIRGAP")
      (footprint "eagle-import:SOIC-08(WIDE,0.295_)-AIRGAP")
      (fields (field (name "MANUFACTURER") "Texas Instruments") (field (name "MPN") "ISO224BDWVR"))
      (libsource (lib "eagle-import") (part "ISO224_AIRGAPB"))
    )
    (comp (ref "U4")
      (value "ISO224B_AIRGAP")
      (footprint "eagle-import:SOIC-08(WIDE,0.295_)-AIRGAP")
      (fields (field (name "MANUFACTURER") "Texas Instruments") (field (name "MPN") "ISO224BDWVR"))
      (libsource (lib "eagle-import") (part "ISO224_AIRGAPB"))
    )
  )
  (nets
    (net (code "1") (name "+5V") (class "Default")
      (node (ref "+5V") (pin "1") (pinfunction "1_1") (pintype "passive"))
      (node (ref "A1") (pin "3") (pinfunction "OUT_3") (pintype "power_in"))
      (node (ref "C19") (pin "1") (pinfunction "1_1") (pintype "passive"))
      (node (ref "C20") (pin "1") (pinfunction "1_1") (pintype "passive"))
      (node (ref "C21") (pin "1") (pinfunction "1_1") (pintype "passive"))
      (node (ref "C22") (pin "1") (pinfunction "1_1") (pintype "passive"))
      (node (ref "C23") (pin "1") (pinfunction "1_1") (pintype "passive"))
      (node (ref "C24") (pin "1") (pinfunction "1_1") (pintype "passive"))
      (node (ref "C25") (pin "1") (pinfunction "1_1") (pintype "passive"))
      (node (ref "R26") (pin "1") (pinfunction "1_1") (pintype "passive"))
      (node (ref "R35") (pin "2") (pinfunction "2_2") (pintype "passive"))
      (node (ref "U10") (pin "5") (pinfunction "V+_5") (pintype "power_in"))
      (node (ref "U3") (pin "8") (pinfunction "VDD2_8") (pintype "power_in"))
      (node (ref "U4") (pin "8") (pinfunction "VDD2_8") (pintype "power_in"))
    )
    (net (code "2") (name "+24V") (class "Default")
      (node (ref "+24V") (pin "1") (pinfunction "1_1") (pintype "passive"))
      (node (ref "A1") (pin "1") (pinfunction "IN_1") (pintype "power_in"))
      (node (ref "C26") (pin "1") (pinfunction "1_1") (pintype "passive"))
      (node (ref "C27") (pin "1") (pinfunction "1_1") (pintype "passive"))
      (node (ref "J3") (pin "1") (pinfunction "1_1") (pintype "passive"))
      (node (ref "R25") (pin "2") (pinfunction "2_2") (pintype "passive"))
    )
    (net (code "3") (name "DCDC_ENABLE") (class "Default")
      (node (ref "D7") (pin "3") (pinfunction "C_3") (pintype "passive"))
      (node (ref "R28") (pin "2") (pinfunction "2_2") (pintype "passive"))
      (node (ref "R31") (pin "2") (pinfunction "2_2") (pintype "passive"))
      (node (ref "R33") (pin "1") (pinfunction "1_1") (pintype "passive"))
      (node (ref "U10") (pin "4") (pinfunction "OUT_4") (pintype "bidirectional"))
    )
    (net (code "4") (name "GND") (class "Default")
      (node (ref "A1") (pin "2") (pinfunction "GND_2") (pintype "power_in"))
      (node (ref "C19") (pin "2") (pinfunction "2_2") (pintype "passive"))
      (node (ref "C20") (pin "2") (pinfunction "2_2") (pintype "passive"))
      (node (ref "C21") (pin "2") (pinfunction "2_2") (pintype "passive"))
      (node (ref "C22") (pin "2") (pinfunction "2_2") (pintype "passive"))
      (node (ref "C23") (pin "2") (pinfunction "2_2") (pintype "passive"))
      (node (ref "C24") (pin "2") (pinfunction "2_2") (pintype "passive"))
      (node (ref "C25") (pin "2") (pinfunction "2_2") (pintype "passive"))
      (node (ref "C26") (pin "2") (pinfunction "2_2") (pintype "passive"))
      (node (ref "C27") (pin "2") (pinfunction "2_2") (pintype "passive"))
      (node (ref "D3") (pin "1") (pinfunction "C_1") (pintype "passive"))
      (node (ref "D4") (pin "1") (pinfunction "C_1") (pintype "passive"))
      (node (ref "D5") (pin "1") (pinfunction "C_1") (pintype "passive"))
      (node (ref "D6") (pin "1") (pinfunction "C_1") (pintype "passive"))
      (node (ref "D7") (pin "1") (pinfunction "A_1") (pintype "passive"))
      (node (ref "D8") (pin "1") (pinfunction "C_1") (pintype "passive"))
      (node (ref "GND") (pin "1") (pinfunction "1_1") (pintype "passive"))
      (node (ref "J3") (pin "4") (pinfunction "4_4") (pintype "passive"))
      (node (ref "Q2") (pin "2") (pinfunction "S_2") (pintype "passive"))
      (node (ref "R28") (pin "1") (pinfunction "1_1") (pintype "passive"))
      (node (ref "R32") (pin "1") (pinfunction "1_1") (pintype "passive"))
      (node (ref "R34") (pin "1") (pinfunction "1_1") (pintype "passive"))
      (node (ref "U10") (pin "2") (pinfunction "GND_2") (pintype "power_in"))
      (node (ref "U3") (pin "5") (pinfunction "GND2_5") (pintype "power_in"))
      (node (ref "U4") (pin "5") (pinfunction "GND2_5") (pintype "power_in"))
      (node (ref "U5") (pin "2") (pinfunction "CONTROL-_2") (pintype "passive"))
    )
    (net (code "5") (name "IP+") (class "Default")
      (node (ref "IP+") (pin "1") (pinfunction "1_1") (pintype "passive"))
      (node (ref "J3") (pin "5") (pinfunction "5_5") (pintype "passive"))
      (node (ref "U4") (pin "7") (pinfunction "OUTP_7") (pintype "output"))
    )
    (net (code "6") (name "IP-") (class "Default")
      (node (ref "IP-") (pin "1") (pinfunction "1_1") (pintype "passive"))
      (node (ref "J3") (pin "6") (pinfunction "6_6") (pintype "passive"))
      (node (ref "U4") (pin "6") (pinfunction "OUTN_6") (pintype "output"))
    )
    (net (code "7") (name "IT+") (class "Default")
      (node (ref "IT+") (pin "1") (pinfunction "1_1") (pintype "passive"))
      (node (ref "J3") (pin "7") (pinfunction "7_7") (pintype "passive"))
      (node (ref "U3") (pin "7") (pinfunction "OUTP_7") (pintype "output"))
    )
    (net (code "8") (name "IT-") (class "Default")
      (node (ref "IT-") (pin "1") (pinfunction "1_1") (pintype "passive"))
      (node (ref "J3") (pin "8") (pinfunction "8_8") (pintype "passive"))
      (node (ref "U3") (pin "6") (pinfunction "OUTN_6") (pintype "output"))
    )
    (net (code "9") (name "LED+") (class "Default")
      (node (ref "J2") (pin "3") (pinfunction "3_3") (pintype "passive"))
      (node (ref "R20") (pin "2") (pinfunction "2_2") (pintype "passive"))
    )
    (net (code "10") (name "Net-(C2-Pad2)") (class "Default")
      (node (ref "C2") (pin "2") (pinfunction "2_2") (pintype "passive"))
      (node (ref "R3") (pin "2") (pinfunction "2_2") (pintype "passive"))
    )
    (net (code "11") (name "Net-(C9-Pad1)") (class "Default")
      (node (ref "C9") (pin "1") (pinfunction "1_1") (pintype "passive"))
      (node (ref "R7") (pin "1") (pinfunction "1_1") (pintype "passive"))
    )
    (net (code "12") (name "Net-(CV1-Pad2)") (class "Default")
      (node (ref "CV1") (pin "2") (pinfunction "2_2") (pintype "passive"))
      (node (ref "R36") (pin "2") (pinfunction "2_2") (pintype "passive"))
    )
    (net (code "13") (name "Net-(D1-A)") (class "Default")
      (node (ref "C2") (pin "1") (pinfunction "1_1") (pintype "passive"))
      (node (ref "D1") (pin "1") (pinfunction "A_1") (pintype "passive"))
      (node (ref "R5") (pin "2") (pinfunction "2_2") (pintype "passive"))
      (node (ref "T1") (pin "5") (pinfunction "5_5") (pintype "bidirectional"))
    )
    (net (code "14") (name "Net-(D1-C)") (class "Default")
      (node (ref "C4") (pin "1") (pinfunction "1_1") (pintype "passive"))
      (node (ref "D1") (pin "2") (pinfunction "C_2") (pintype "passive"))
      (node (ref "U2") (pin "9") (pinfunction "BIAS_9") (pintype "bidirectional"))
    )
    (net (code "15") (name "Net-(D3-A)") (class "Default")
      (node (ref "D3") (pin "2") (pinfunction "A_2") (pintype "passive"))
      (node (ref "R25") (pin "1") (pinfunction "1_1") (pintype "passive"))
    )
    (net (code "16") (name "Net-(D4-A)") (class "Default")
      (node (ref "D4") (pin "2") (pinfunction "A_2") (pintype "passive"))
      (node (ref "R26") (pin "2") (pinfunction "2_2") (pintype "passive"))
    )
    (net (code "17") (name "Net-(D5-A)") (class "Default")
      (node (ref "D5") (pin "2") (pinfunction "A_2") (pintype "passive"))
      (node (ref "R27") (pin "1") (pinfunction "1_1") (pintype "passive"))
    )
    (net (code "18") (name "Net-(D6-A)") (class "Default")
      (node (ref "D6") (pin "2") (pinfunction "A_2") (pintype "passive"))
      (node (ref "R29") (pin "1") (pinfunction "1_1") (pintype "passive"))
    )
    (net (code "19") (name "Net-(D8-A)") (class "Default")
      (node (ref "D8") (pin "2") (pinfunction "A_2") (pintype "passive"))
      (node (ref "R31") (pin "1") (pinfunction "1_1") (pintype "passive"))
    )
    (net (code "20") (name "Net-(D101-A)") (class "Default")
      (node (ref "D101") (pin "1") (pinfunction "A_1") (pintype "passive"))
      (node (ref "R36") (pin "1") (pinfunction "1_1") (pintype "passive"))
      (node (ref "T1") (pin "8") (pinfunction "8,9_8") (pintype "bidirectional"))
      (node (ref "T1") (pin "9") (pinfunction "8,9_9") (pintype "bidirectional"))
    )
    (net (code "21") (name "Net-(D102-C)") (class "Default")
      (node (ref "D102") (pin "2") (pinfunction "C_2") (pintype "passive"))
      (node (ref "D103") (pin "C") (pinfunction "C_C") (pintype "passive"))
    )
    (net (code "22") (name "Net-(D103-PadA)") (class "Default")
      (node (ref "D103") (pin "A") (pinfunction "A_A") (pintype "passive"))
      (node (ref "Q1") (pin "D") (pinfunction "D_D") (pintype "passive"))
      (node (ref "T1") (pin "1") (pinfunction "1_1") (pintype "bidirectional"))
    )
    (net (code "23") (name "Net-(K1-COIL-)") (class "Default")
      (node (ref "D100") (pin "A") (pinfunction "A_A") (pintype "passive"))
      (node (ref "K1") (pin "3") (pinfunction "COIL-_3") (pintype "bidirectional"))
      (node (ref "Q2") (pin "3") (pinfunction "D_3") (pintype "passive"))
    )
    (net (code "24") (name "Net-(K1-CONTACT2)") (class "Default")
      (node (ref "K1") (pin "1") (pinfunction "CONTACT2_1") (pintype "bidirectional"))
      (node (ref "R13") (pin "1") (pinfunction "1_1") (pintype "passive"))
      (node (ref "R23") (pin "1") (pinfunction "1_1") (pintype "passive"))
    )
    (net (code "25") (name "Net-(LED_+12V-A)") (class "Default")
      (node (ref "LED_+12V") (pin "2") (pinfunction "A_2") (pintype "passive"))
      (node (ref "R1") (pin "1") (pinfunction "1_1") (pintype "passive"))
    )
    (net (code "26") (name "Net-(Q1-PadG)") (class "Default")
      (node (ref "Q1") (pin "G") (pinfunction "G_G") (pintype "passive"))
      (node (ref "R4") (pin "2") (pinfunction "2_2") (pintype "passive"))
    )
    (net (code "27") (name "Net-(Q2-G)") (class "Default")
      (node (ref "Q2") (pin "1") (pinfunction "G_1") (pintype "passive"))
      (node (ref "R33") (pin "2") (pinfunction "2_2") (pintype "passive"))
    )
    (net (code "28") (name "Net-(R10-Pad2)") (class "Default")
      (node (ref "R10") (pin "2") (pinfunction "2_2") (pintype "passive"))
      (node (ref "R11") (pin "1") (pinfunction "1_1") (pintype "passive"))
    )
    (net (code "29") (name "Net-(R11-Pad2)") (class "Default")
      (node (ref "R11") (pin "2") (pinfunction "2_2") (pintype "passive"))
      (node (ref "R9") (pin "1") (pinfunction "1_1") (pintype "passive"))
    )
    (net (code "30") (name "Net-(R19-Pad2)") (class "Default")
      (node (ref "R19") (pin "2") (pinfunction "2_2") (pintype "passive"))
      (node (ref "R21") (pin "1") (pinfunction "1_1") (pintype "passive"))
    )
    (net (code "31") (name "Net-(R21-Pad2)") (class "Default")
      (node (ref "R21") (pin "2") (pinfunction "2_2") (pintype "passive"))
      (node (ref "R22") (pin "1") (pinfunction "1_1") (pintype "passive"))
    )
    (net (code "32") (name "Net-(U2-DCM)") (class "Default")
      (node (ref "R3") (pin "1") (pinfunction "1_1") (pintype "passive"))
      (node (ref "U2") (pin "10") (pinfunction "DCM_10") (pintype "bidirectional"))
    )
    (net (code "33") (name "Net-(U2-EN{slash}UVLO)") (class "Default")
      (node (ref "C6") (pin "1") (pinfunction "1_1") (pintype "passive"))
      (node (ref "U2") (pin "17") (pinfunction "EN/UVLO_17") (pintype "bidirectional"))
      (node (ref "U2") (pin "8") (pinfunction "INTVCC_8") (pintype "bidirectional"))
    )
    (net (code "34") (name "Net-(U2-FB)") (class "Default")
      (node (ref "R5") (pin "1") (pinfunction "1_1") (pintype "passive"))
      (node (ref "R6") (pin "2") (pinfunction "2_2") (pintype "passive"))
      (node (ref "U2") (pin "12") (pinfunction "FB_12") (pintype "bidirectional"))
    )
    (net (code "35") (name "Net-(U2-GATE)") (class "Default")
      (node (ref "R4") (pin "1") (pinfunction "1_1") (pintype "passive"))
      (node (ref "U2") (pin "19") (pinfunction "GATE_19") (pintype "bidirectional"))
    )
    (net (code "36") (name "Net-(U2-IREG)") (class "Default")
      (node (ref "R12") (pin "2") (pinfunction "2_2") (pintype "passive"))
      (node (ref "U2") (pin "14") (pinfunction "IREG_14") (pintype "bidirectional"))
    )
    (net (code "37") (name "Net-(U2-SENSE)") (class "Default")
      (node (ref "Q1") (pin "S") (pinfunction "S_S") (pintype "passive"))
      (node (ref "R2") (pin "2") (pinfunction "2_2") (pintype "passive"))
      (node (ref "U2") (pin "18") (pinfunction "SENSE_18") (pintype "bidirectional"))
    )
    (net (code "38") (name "Net-(U2-VC)") (class "Default")
      (node (ref "R7") (pin "2") (pinfunction "2_2") (pintype "passive"))
      (node (ref "U2") (pin "13") (pinfunction "VC_13") (pintype "bidirectional"))
    )
    (net (code "39") (name "Net-(U3-IN)") (class "Default")
      (node (ref "C12") (pin "1") (pinfunction "1_1") (pintype "passive"))
      (node (ref "R15") (pin "2") (pinfunction "2_2") (pintype "passive"))
      (node (ref "U3") (pin "2") (pinfunction "IN_2") (pintype "input"))
    )
    (net (code "40") (name "Net-(U3-VCAP)") (class "Default")
      (node (ref "C16") (pin "1") (pinfunction "1_1") (pintype "passive"))
      (node (ref "U3") (pin "1") (pinfunction "VCAP_1") (pintype "passive"))
    )
    (net (code "41") (name "Net-(U4-IN)") (class "Default")
      (node (ref "C10") (pin "1") (pinfunction "1_1") (pintype "passive"))
      (node (ref "R18") (pin "2") (pinfunction "2_2") (pintype "passive"))
      (node (ref "U4") (pin "2") (pinfunction "IN_2") (pintype "input"))
    )
    (net (code "42") (name "Net-(U4-VCAP)") (class "Default")
      (node (ref "C17") (pin "1") (pinfunction "1_1") (pintype "passive"))
      (node (ref "U4") (pin "1") (pinfunction "VCAP_1") (pintype "passive"))
    )
    (net (code "43") (name "Net-(U5-CONTACT1)") (class "Default")
      (node (ref "R24") (pin "1") (pinfunction "1_1") (pintype "passive"))
      (node (ref "U5") (pin "3") (pinfunction "CONTACT1_3") (pintype "bidirectional"))
    )
    (net (code "44") (name "Net-(U5-CONTROL+)") (class "Default")
      (node (ref "R30") (pin "2") (pinfunction "2_2") (pintype "passive"))
      (node (ref "U5") (pin "1") (pinfunction "CONTROL+_1") (pintype "passive"))
    )
    (net (code "45") (name "Net-(U10-DIV)") (class "Default")
      (node (ref "R34") (pin "2") (pinfunction "2_2") (pintype "passive"))
      (node (ref "R35") (pin "1") (pinfunction "1_1") (pintype "passive"))
      (node (ref "U10") (pin "6") (pinfunction "DIV_6") (pintype "bidirectional"))
    )
    (net (code "46") (name "Net-(U10-SET)") (class "Default")
      (node (ref "R32") (pin "2") (pinfunction "2_2") (pintype "passive"))
      (node (ref "U10") (pin "3") (pinfunction "SET_3") (pintype "bidirectional"))
    )
    (net (code "47") (name "PACK+") (class "Default")
      (node (ref "J1") (pin "5") (pinfunction "5_5") (pintype "passive"))
      (node (ref "K1") (pin "2") (pinfunction "CONTACT1_2") (pintype "bidirectional"))
      (node (ref "PACK+") (pin "1") (pinfunction "1_1") (pintype "passive"))
      (node (ref "U5") (pin "4") (pinfunction "CONTACT2_4") (pintype "bidirectional"))
    )
    (net (code "48") (name "PACK+FUSED") (class "Default")
      (node (ref "PACK+FUSED") (pin "1") (pinfunction "1_1") (pintype "passive"))
      (node (ref "R22") (pin "2") (pinfunction "2_2") (pintype "passive"))
      (node (ref "R24") (pin "2") (pinfunction "2_2") (pintype "passive"))
    )
    (net (code "49") (name "PACK_DIV_OUT") (class "Default")
      (node (ref "PACK_DIV_OUT") (pin "1") (pinfunction "1_1") (pintype "passive"))
      (node (ref "R16") (pin "2") (pinfunction "2_2") (pintype "passive"))
      (node (ref "R17") (pin "2") (pinfunction "2_2") (pintype "passive"))
      (node (ref "R18") (pin "1") (pinfunction "1_1") (pintype "passive"))
      (node (ref "R19") (pin "1") (pinfunction "1_1") (pintype "passive"))
    )
    (net (code "50") (name "PRECHARGE_OK") (class "Default")
      (node (ref "J3") (pin "3") (pinfunction "3_3") (pintype "passive"))
      (node (ref "PRECHARGE_OK") (pin "1") (pinfunction "1_1") (pintype "passive"))
      (node (ref "R29") (pin "2") (pinfunction "2_2") (pintype "passive"))
      (node (ref "U10") (pin "1") (pinfunction "IN_1") (pintype "bidirectional"))
    )
    (net (code "51") (name "SHDN") (class "Default")
      (node (ref "D100") (pin "C") (pinfunction "C_C") (pintype "passive"))
      (node (ref "J3") (pin "2") (pinfunction "2_2") (pintype "passive"))
      (node (ref "K1") (pin "4") (pinfunction "COIL+_4") (pintype "bidirectional"))
      (node (ref "R27") (pin "2") (pinfunction "2_2") (pintype "passive"))
      (node (ref "R30") (pin "1") (pinfunction "1_1") (pintype "passive"))
      (node (ref "SHDN") (pin "1") (pinfunction "1_1") (pintype "passive"))
    )
    (net (code "52") (name "TS+10V") (class "Default")
      (node (ref "C11") (pin "1") (pinfunction "1_1") (pintype "passive"))
      (node (ref "C13") (pin "1") (pinfunction "1_1") (pintype "passive"))
      (node (ref "C15") (pin "1") (pinfunction "1_1") (pintype "passive"))
      (node (ref "C18") (pin "1") (pinfunction "1_1") (pintype "passive"))
      (node (ref "C5") (pin "1") (pinfunction "1_1") (pintype "passive"))
      (node (ref "TS+10V") (pin "1") (pinfunction "1_1") (pintype "passive"))
      (node (ref "U1") (pin "2") (pinfunction "OUT_2") (pintype "power_in"))
      (node (ref "U1") (pin "4") (pinfunction "OUT_4") (pintype "power_in"))
      (node (ref "U3") (pin "3") (pinfunction "VDD1_3") (pintype "power_in"))
      (node (ref "U4") (pin "3") (pinfunction "VDD1_3") (pintype "power_in"))
    )
    (net (code "53") (name "TS+12V") (class "Default")
      (node (ref "C1") (pin "1") (pinfunction "1_1") (pintype "passive"))
      (node (ref "C28") (pin "PLUS") (pinfunction "PLUS_PLUS") (pintype "passive"))
      (node (ref "C7") (pin "1") (pinfunction "1_1") (pintype "passive"))
      (node (ref "C8") (pin "1") (pinfunction "1_1") (pintype "passive"))
      (node (ref "CV1") (pin "1") (pinfunction "1_1") (pintype "passive"))
      (node (ref "D101") (pin "2") (pinfunction "C_2") (pintype "passive"))
      (node (ref "R1") (pin "2") (pinfunction "2_2") (pintype "passive"))
      (node (ref "R20") (pin "1") (pinfunction "1_1") (pintype "passive"))
      (node (ref "TS+12V") (pin "1") (pinfunction "1_1") (pintype "passive"))
      (node (ref "U1") (pin "3") (pinfunction "IN_3") (pintype "power_in"))
    )
    (net (code "54") (name "TS+FUSED") (class "Default")
      (node (ref "C14") (pin "1") (pinfunction "1_1") (pintype "passive"))
      (node (ref "D102") (pin "1") (pinfunction "A_1") (pintype "passive"))
      (node (ref "F1") (pin "3") (pinfunction "2_3") (pintype "passive"))
      (node (ref "F1") (pin "4") (pinfunction "2_4") (pintype "passive"))
      (node (ref "J1") (pin "4") (pinfunction "4_4") (pintype "passive"))
      (node (ref "R9") (pin "2") (pinfunction "2_2") (pintype "passive"))
      (node (ref "T1") (pin "3") (pinfunction "3_3") (pintype "bidirectional"))
      (node (ref "U2") (pin "1") (pinfunction "VIN_1") (pintype "input"))
      (node (ref "U2") (pin "2") (pinfunction "VIN_2") (pintype "input"))
      (node (ref "U2") (pin "3") (pinfunction "VIN_3") (pintype "input"))
    )
    (net (code "55") (name "TS+UNFUSED") (class "Default")
      (node (ref "F1") (pin "1") (pinfunction "1_1") (pintype "passive"))
      (node (ref "F1") (pin "2") (pinfunction "1_2") (pintype "passive"))
      (node (ref "J1") (pin "1") (pinfunction "1_1") (pintype "passive"))
      (node (ref "J1") (pin "2") (pinfunction "2_2") (pintype "passive"))
      (node (ref "R13") (pin "2") (pinfunction "2_2") (pintype "passive"))
      (node (ref "R23") (pin "2") (pinfunction "2_2") (pintype "passive"))
    )
    (net (code "56") (name "TS-FUSED") (class "Default")
      (node (ref "C1") (pin "2") (pinfunction "2_2") (pintype "passive"))
      (node (ref "C10") (pin "2") (pinfunction "2_2") (pintype "passive"))
      (node (ref "C11") (pin "2") (pinfunction "2_2") (pintype "passive"))
      (node (ref "C12") (pin "2") (pinfunction "2_2") (pintype "passive"))
      (node (ref "C13") (pin "2") (pinfunction "2_2") (pintype "passive"))
      (node (ref "C14") (pin "2") (pinfunction "2_2") (pintype "passive"))
      (node (ref "C15") (pin "2") (pinfunction "2_2") (pintype "passive"))
      (node (ref "C16") (pin "2") (pinfunction "2_2") (pintype "passive"))
      (node (ref "C17") (pin "2") (pinfunction "2_2") (pintype "passive"))
      (node (ref "C18") (pin "2") (pinfunction "2_2") (pintype "passive"))
      (node (ref "C28") (pin "MINUS") (pinfunction "MINUS_MINUS") (pintype "passive"))
      (node (ref "C4") (pin "2") (pinfunction "2_2") (pintype "passive"))
      (node (ref "C5") (pin "2") (pinfunction "2_2") (pintype "passive"))
      (node (ref "C6") (pin "2") (pinfunction "2_2") (pintype "passive"))
      (node (ref "C7") (pin "2") (pinfunction "2_2") (pintype "passive"))
      (node (ref "C8") (pin "2") (pinfunction "2_2") (pintype "passive"))
      (node (ref "C9") (pin "2") (pinfunction "2_2") (pintype "passive"))
      (node (ref "F2") (pin "3") (pinfunction "2_3") (pintype "passive"))
      (node (ref "F2") (pin "4") (pinfunction "2_4") (pintype "passive"))
      (node (ref "J2") (pin "1") (pinfunction "1_1") (pintype "passive"))
      (node (ref "J2") (pin "2") (pinfunction "2_2") (pintype "passive"))
      (node (ref "LED_+12V") (pin "1") (pinfunction "C_1") (pintype "passive"))
      (node (ref "R12") (pin "1") (pinfunction "1_1") (pintype "passive"))
      (node (ref "R14") (pin "1") (pinfunction "1_1") (pintype "passive"))
      (node (ref "R16") (pin "1") (pinfunction "1_1") (pintype "passive"))
      (node (ref "R17") (pin "1") (pinfunction "1_1") (pintype "passive"))
      (node (ref "R2") (pin "1") (pinfunction "1_1") (pintype "passive"))
      (node (ref "R6") (pin "1") (pinfunction "1_1") (pintype "passive"))
      (node (ref "R8") (pin "1") (pinfunction "1_1") (pintype "passive"))
      (node (ref "T1") (pin "10") (pinfunction "10,11_10") (pintype "bidirectional"))
      (node (ref "T1") (pin "11") (pinfunction "10,11_11") (pintype "bidirectional"))
      (node (ref "T1") (pin "6") (pinfunction "6_6") (pintype "bidirectional"))
      (node (ref "TS-FUSED") (pin "1") (pinfunction "1_1") (pintype "passive"))
      (node (ref "U1") (pin "1") (pinfunction "GND_1") (pintype "power_in"))
      (node (ref "U2") (pin "15") (pinfunction "GND_15") (pintype "bidirectional"))
      (node (ref "U2") (pin "16") (pinfunction "SMODE_16") (pintype "bidirectional"))
      (node (ref "U2") (pin "20") (pinfunction "GND_20") (pintype "bidirectional"))
      (node (ref "U2") (pin "THERMAL") (pinfunction "P$1_THERMAL") (pintype "output"))
      (node (ref "U3") (pin "4") (pinfunction "GND1_4") (pintype "power_in"))
      (node (ref "U4") (pin "4") (pinfunction "GND1_4") (pintype "power_in"))
    )
    (net (code "57") (name "TS-UNFUSED") (class "Default")
      (node (ref "F2") (pin "1") (pinfunction "1_1") (pintype "passive"))
      (node (ref "F2") (pin "2") (pinfunction "1_2") (pintype "passive"))
      (node (ref "J2") (pin "5") (pinfunction "5_5") (pintype "passive"))
      (node (ref "TS-UNFUSED") (pin "1") (pinfunction "1_1") (pintype "passive"))
    )
    (net (code "58") (name "TS_DIV_OUT") (class "Default")
      (node (ref "R10") (pin "1") (pinfunction "1_1") (pintype "passive"))
      (node (ref "R14") (pin "2") (pinfunction "2_2") (pintype "passive"))
      (node (ref "R15") (pin "1") (pinfunction "1_1") (pintype "passive"))
      (node (ref "R8") (pin "2") (pinfunction "2_2") (pintype "passive"))
      (node (ref "TS_DIV_OUT") (pin "1") (pinfunction "1_1") (pintype "passive"))
    )
    (net (code "59") (name "unconnected-(J1-Pad3)") (class "Default")
      (node (ref "J1") (pin "3") (pinfunction "3_3") (pintype "passive"))
    )
    (net (code "60") (name "unconnected-(J2-Pad4)") (class "Default")
      (node (ref "J2") (pin "4") (pinfunction "4_4") (pintype "passive"))
    )
    (net (code "61") (name "unconnected-(U2-TC-Pad11)") (class "Default")
      (node (ref "U2") (pin "11") (pinfunction "TC_11") (pintype "bidirectional"))
    )
  )
)
